# DryContact.net
KiCad netlist of a schematic drawn in Altium Designer
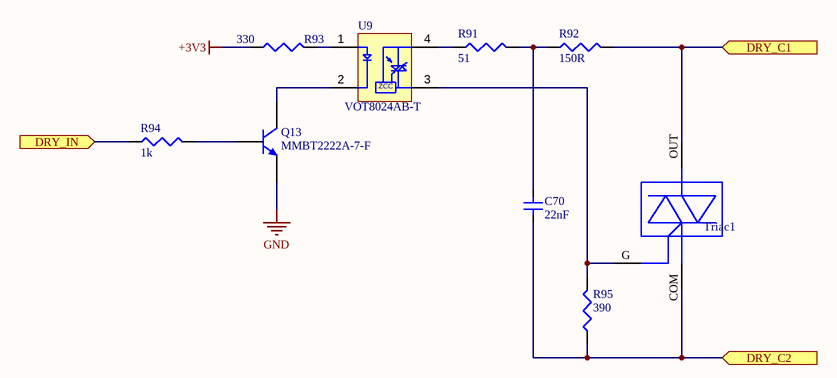
[diagram p0: DryContact.SchDoc]

(export (version "E")
  (design (tool "Eeschema 10.0.6"))
  (components
    (comp (ref "C70")
      (value "22nF")
      (footprint "1206")
      (description "Capacitor SMD Ceramic 1206 400Vdc X7R Dielectric 0.022uF ±10% 125°C T/R")
      (fields
        (field (name "MANUFACTURER") "Kyocera AVX")
        (field (name "MANUFACTURER PART NUMBER") "12068C223KAT2A")
      )
      (libsource (lib "Kish Spark") (part "C0805C472K5RAC7210_1"))
    )
    (comp (ref "Q13")
      (value "MMBT2222A-7-F")
      (footprint "SOT23127P600-8N")
      (description "MMBT2222 Series NPN 350 mW 40 V 600 mA SMT Small Signal Transistor - SOT-23")
      (fields
        (field (name "MANUFACTURER") "Diodes")
        (field (name "VOLTAGE") "40V")
        (field (name "SOURCE") "PTZ.SCHLIB")
      )
      (libsource (lib "Kish Spark") (part "BJT-NPN-EBC-3"))
    )
    (comp (ref "R91")
      (value "51")
      (footprint "R0603")
      (description "Thick Film Resistors - SMD 0.2W 51ohm 1% 100ppm")
      (fields
        (field (name "TOLERANCE") "1%")
        (field (name "Comment") "CMP-009-00208-1")
        (field (name "SOURCE") "PTZLib.SchLib")
      )
      (libsource (lib "Kish Spark") (part "RN73R1JTTD3302F10"))
    )
    (comp (ref "R92")
      (value "150R")
      (footprint "R0603")
      (fields (field (name "Comment") "CMP-009-00192-1") (field (name "SOURCE") "PTZLib.SchLib"))
      (libsource (lib "Kish Spark") (part "RN73R1JTTD3302F10"))
    )
    (comp (ref "R93")
      (value "330")
      (footprint "R0603")
      (description "Res Thick Film 0603 330 Ohm 1% 0.1W(1/10W) ±100ppm/C Pad SMD T/R")
      (fields (field (name "TOLERANCE") "1%") (field (name "MANUFACTURER") "Yageo"))
      (libsource (lib "Kish Spark") (part "CRCW06030000Z0EAHP"))
    )
    (comp (ref "R94")
      (value "1k")
      (footprint "R0603")
      (description "Res Thick Film 0603 1K Ohm 1% 1/10W ±100ppm/°C Molded SMD Paper T/R")
      (fields
        (field (name "MANUFACTURER") "Yageo")
        (field (name "MANUFACTURER PART NUMBER") "AC0603FR-071KL")
        (field (name "SOURCE") "PTZLib.SchLib")
      )
      (libsource (lib "Kish Spark") (part "RN73R1JTTD3302F10"))
    )
    (comp (ref "R95")
      (value "390")
      (footprint "R0603")
      (description "Res Thick Film 0603 390 Ohm 1% 1/10W 100ppm/C Molded SMD Paper T/R")
      (fields
        (field (name "TOLERANCE") "1%")
        (field (name "Comment") "CMP-009-00224-1")
        (field (name "SOURCE") "PTZLib.SchLib")
      )
      (libsource (lib "Kish Spark") (part "RN73R1JTTD3302F10"))
    )
    (comp (ref "Triac1")
      (value "ACST210-8BTR")
      (footprint "ACST210_DPAK")
      (description "Triacs Triac Crowbar 10mA Switch 2A 800V")
      (fields (field (name "SOURCE") "PTZLib.SchLib"))
      (libsource (lib "Kish Spark") (part "ACST210-8BTR"))
    )
    (comp (ref "U9")
      (value "VOT8024AB-T")
      (footprint "SW-TRIAC")
      (description "Optocoupler Triac AC-OUT 1-Channel 800VDRM 4-Pin Surface Mount T/R")
      (fields (field (name "MANUFACTURER") "Vishay"))
      (libsource (lib "Kish Spark") (part "VOT8024AB-T"))
    )
  )
  (nets
    (net (code "1") (name "+3V3") (class "Default")
      (node (ref "R93") (pin "2") (pinfunction "2_2") (pintype "passive"))
    )
    (net (code "2") (name "/DRY_C1") (class "Default")
      (node (ref "R92") (pin "2") (pinfunction "2_2") (pintype "passive"))
      (node (ref "Triac1") (pin "OUT") (pinfunction "1_OUT") (pintype "passive"))
    )
    (net (code "3") (name "/DRY_C2") (class "Default")
      (node (ref "C70") (pin "1") (pinfunction "1_1") (pintype "passive"))
      (node (ref "R95") (pin "1") (pinfunction "1_1") (pintype "passive"))
      (node (ref "Triac1") (pin "COM") (pinfunction "3_COM") (pintype "passive"))
    )
    (net (code "4") (name "/DRY_IN") (class "Default")
      (node (ref "R94") (pin "1") (pinfunction "1_1") (pintype "passive"))
    )
    (net (code "5") (name "GND") (class "Default")
      (node (ref "Q13") (pin "1") (pinfunction "E_1") (pintype "passive"))
    )
    (net (code "6") (name "Net-(C70-Pad2)") (class "Default")
      (node (ref "C70") (pin "2") (pinfunction "2_2") (pintype "passive"))
      (node (ref "R91") (pin "2") (pinfunction "2_2") (pintype "passive"))
      (node (ref "R92") (pin "1") (pinfunction "1_1") (pintype "passive"))
    )
    (net (code "7") (name "Net-(Q13-B)") (class "Default")
      (node (ref "Q13") (pin "2") (pinfunction "B_2") (pintype "passive"))
      (node (ref "R94") (pin "2") (pinfunction "2_2") (pintype "passive"))
    )
    (net (code "8") (name "Net-(Q13-C)") (class "Default")
      (node (ref "Q13") (pin "3") (pinfunction "C_3") (pintype "passive"))
      (node (ref "U9") (pin "2") (pinfunction "C_2") (pintype "passive"))
    )
    (net (code "9") (name "Net-(Triac1-2)") (class "Default")
      (node (ref "R95") (pin "2") (pinfunction "2_2") (pintype "passive"))
      (node (ref "Triac1") (pin "G") (pinfunction "2_G") (pintype "passive"))
      (node (ref "U9") (pin "3") (pinfunction "MT1_3") (pintype "passive"))
    )
    (net (code "10") (name "Net-(U9-A)") (class "Default")
      (node (ref "R93") (pin "1") (pinfunction "1_1") (pintype "passive"))
      (node (ref "U9") (pin "1") (pinfunction "A_1") (pintype "passive"))
    )
    (net (code "11") (name "Net-(U9-MT2)") (class "Default")
      (node (ref "R91") (pin "1") (pinfunction "1_1") (pintype "passive"))
      (node (ref "U9") (pin "4") (pinfunction "MT2_4") (pintype "passive"))
    )
  )
)
